# USBasp_B.net
KiCad netlist of a schematic drawn in EAGLE
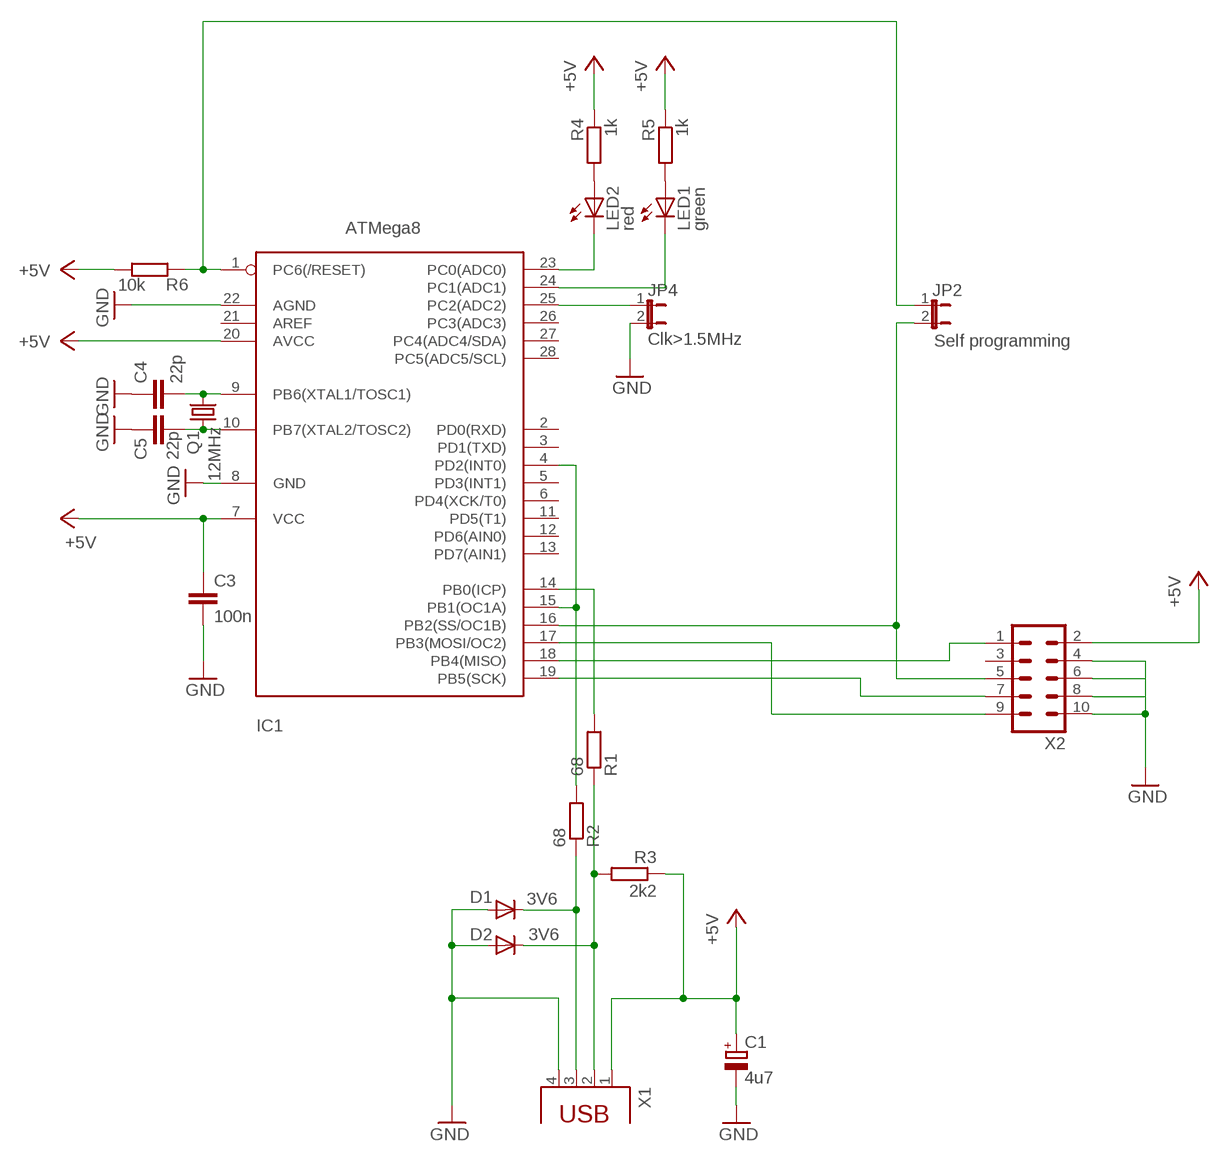
[diagram p0: schematic, sheet 1]

(export (version "E")
  (design (tool "Eeschema 10.0.6"))
  (components
    (comp (ref "C1")
      (value "4u7")
      (footprint "eagle-import:E2,5-5")
      (libsource (lib "eagle-import") (part "CPOL-EUE2.5-5"))
    )
    (comp (ref "C3")
      (value "100n")
      (footprint "eagle-import:C1206K")
      (libsource (lib "eagle-import") (part "C-EUC1206K"))
    )
    (comp (ref "C4")
      (value "22p")
      (footprint "eagle-import:C1206K")
      (libsource (lib "eagle-import") (part "C-EUC1206K"))
    )
    (comp (ref "C5")
      (value "22p")
      (footprint "eagle-import:C1206K")
      (libsource (lib "eagle-import") (part "C-EUC1206K"))
    )
    (comp (ref "D1")
      (value "3V6")
      (footprint "eagle-import:SOD80C")
      (libsource (lib "eagle-import") (part "PMLL41SOD80C"))
    )
    (comp (ref "D2")
      (value "3V6")
      (footprint "eagle-import:SOD80C")
      (libsource (lib "eagle-import") (part "PMLL41SOD80C"))
    )
    (comp (ref "IC1")
      (value "ATMega8")
      (footprint "eagle-import:DIL28-3")
      (libsource (lib "eagle-import") (part "MEGA8-P"))
    )
    (comp (ref "JP2")
      (value "Self programming")
      (footprint "eagle-import:JP1")
      (libsource (lib "eagle-import") (part "JP1E"))
    )
    (comp (ref "JP4")
      (value "Clk>1.5MHz")
      (footprint "eagle-import:JP1")
      (libsource (lib "eagle-import") (part "JP1E"))
    )
    (comp (ref "LED1")
      (value "green")
      (footprint "eagle-import:LED3MM")
      (libsource (lib "eagle-import") (part "LED3MM"))
    )
    (comp (ref "LED2")
      (value "red")
      (footprint "eagle-import:LED3MM")
      (libsource (lib "eagle-import") (part "LED3MM"))
    )
    (comp (ref "Q1")
      (value "12MHz")
      (footprint "eagle-import:HC49_S")
      (libsource (lib "eagle-import") (part "CRYTALHC49S"))
    )
    (comp (ref "R1")
      (value "68")
      (footprint "eagle-import:R1206W")
      (libsource (lib "eagle-import") (part "R-EU_R1206W"))
    )
    (comp (ref "R2")
      (value "68")
      (footprint "eagle-import:R1206W")
      (libsource (lib "eagle-import") (part "R-EU_R1206W"))
    )
    (comp (ref "R3")
      (value "2k2")
      (footprint "eagle-import:R1206W")
      (libsource (lib "eagle-import") (part "R-EU_R1206W"))
    )
    (comp (ref "R4")
      (value "1k")
      (footprint "eagle-import:R1206W")
      (libsource (lib "eagle-import") (part "R-EU_R1206W"))
    )
    (comp (ref "R5")
      (value "1k")
      (footprint "eagle-import:R1206W")
      (libsource (lib "eagle-import") (part "R-EU_R1206W"))
    )
    (comp (ref "R6")
      (value "10k")
      (footprint "eagle-import:R1206W")
      (libsource (lib "eagle-import") (part "R-EU_R1206W"))
    )
    (comp (ref "X1")
      (value "PN61729")
      (footprint "eagle-import:PN61729")
      (libsource (lib "eagle-import") (part "PN61729"))
    )
    (comp (ref "X2")
      (value "ML10")
      (footprint "eagle-import:ML10")
      (libsource (lib "eagle-import") (part "ML10"))
    )
  )
  (nets
    (net (code "1") (name "+5V") (class "Default")
      (node (ref "C1") (pin "+") (pinfunction "+_+") (pintype "passive"))
      (node (ref "C3") (pin "1") (pinfunction "1_1") (pintype "passive"))
      (node (ref "IC1") (pin "20") (pinfunction "AVCC_20") (pintype "bidirectional"))
      (node (ref "IC1") (pin "7") (pinfunction "VCC_7") (pintype "bidirectional"))
      (node (ref "R3") (pin "1") (pinfunction "1_1") (pintype "passive"))
      (node (ref "R4") (pin "1") (pinfunction "1_1") (pintype "passive"))
      (node (ref "R5") (pin "1") (pinfunction "1_1") (pintype "passive"))
      (node (ref "R6") (pin "1") (pinfunction "1_1") (pintype "passive"))
      (node (ref "X1") (pin "1") (pinfunction "1_1") (pintype "bidirectional"))
      (node (ref "X2") (pin "2") (pinfunction "2_2") (pintype "passive"))
    )
    (net (code "2") (name "GND") (class "Default")
      (node (ref "C1") (pin "-") (pinfunction "-_-") (pintype "passive"))
      (node (ref "C3") (pin "2") (pinfunction "2_2") (pintype "passive"))
      (node (ref "C4") (pin "1") (pinfunction "1_1") (pintype "passive"))
      (node (ref "C5") (pin "1") (pinfunction "1_1") (pintype "passive"))
      (node (ref "D1") (pin "A") (pinfunction "A_A") (pintype "passive"))
      (node (ref "D2") (pin "A") (pinfunction "A_A") (pintype "passive"))
      (node (ref "IC1") (pin "22") (pinfunction "AGND_22") (pintype "bidirectional"))
      (node (ref "IC1") (pin "8") (pinfunction "GND_8") (pintype "bidirectional"))
      (node (ref "JP4") (pin "2") (pinfunction "2_2") (pintype "passive"))
      (node (ref "X1") (pin "4") (pinfunction "4_4") (pintype "bidirectional"))
      (node (ref "X2") (pin "10") (pinfunction "10_10") (pintype "passive"))
      (node (ref "X2") (pin "4") (pinfunction "4_4") (pintype "passive"))
      (node (ref "X2") (pin "6") (pinfunction "6_6") (pintype "passive"))
      (node (ref "X2") (pin "8") (pinfunction "8_8") (pintype "passive"))
    )
    (net (code "3") (name "Net-(D1-PadC)") (class "Default")
      (node (ref "D1") (pin "C") (pinfunction "C_C") (pintype "passive"))
      (node (ref "R2") (pin "1") (pinfunction "1_1") (pintype "passive"))
      (node (ref "X1") (pin "3") (pinfunction "3_3") (pintype "bidirectional"))
    )
    (net (code "4") (name "Net-(D2-PadC)") (class "Default")
      (node (ref "D2") (pin "C") (pinfunction "C_C") (pintype "passive"))
      (node (ref "R1") (pin "1") (pinfunction "1_1") (pintype "passive"))
      (node (ref "R3") (pin "2") (pinfunction "2_2") (pintype "passive"))
      (node (ref "X1") (pin "2") (pinfunction "2_2") (pintype "bidirectional"))
    )
    (net (code "5") (name "Net-(IC1-PB0(ICP))") (class "Default")
      (node (ref "IC1") (pin "14") (pinfunction "PB0(ICP)_14") (pintype "bidirectional"))
      (node (ref "R1") (pin "2") (pinfunction "2_2") (pintype "passive"))
    )
    (net (code "6") (name "Net-(IC1-PB1(OC1A))") (class "Default")
      (node (ref "IC1") (pin "15") (pinfunction "PB1(OC1A)_15") (pintype "bidirectional"))
      (node (ref "IC1") (pin "4") (pinfunction "PD2(INT0)_4") (pintype "bidirectional"))
      (node (ref "R2") (pin "2") (pinfunction "2_2") (pintype "passive"))
    )
    (net (code "7") (name "Net-(IC1-PB2(SS{slash}OC1B))") (class "Default")
      (node (ref "IC1") (pin "16") (pinfunction "PB2(SS/OC1B)_16") (pintype "bidirectional"))
      (node (ref "JP2") (pin "2") (pinfunction "2_2") (pintype "passive"))
      (node (ref "X2") (pin "5") (pinfunction "5_5") (pintype "passive"))
    )
    (net (code "8") (name "Net-(IC1-PB3(MOSI{slash}OC2))") (class "Default")
      (node (ref "IC1") (pin "17") (pinfunction "PB3(MOSI/OC2)_17") (pintype "bidirectional"))
      (node (ref "X2") (pin "9") (pinfunction "9_9") (pintype "passive"))
    )
    (net (code "9") (name "Net-(IC1-PB4(MISO))") (class "Default")
      (node (ref "IC1") (pin "18") (pinfunction "PB4(MISO)_18") (pintype "bidirectional"))
      (node (ref "X2") (pin "1") (pinfunction "1_1") (pintype "passive"))
    )
    (net (code "10") (name "Net-(IC1-PB5(SCK))") (class "Default")
      (node (ref "IC1") (pin "19") (pinfunction "PB5(SCK)_19") (pintype "bidirectional"))
      (node (ref "X2") (pin "7") (pinfunction "7_7") (pintype "passive"))
    )
    (net (code "11") (name "Net-(IC1-PB6(XTAL1{slash}TOSC1))") (class "Default")
      (node (ref "C4") (pin "2") (pinfunction "2_2") (pintype "passive"))
      (node (ref "IC1") (pin "9") (pinfunction "PB6(XTAL1/TOSC1)_9") (pintype "bidirectional"))
      (node (ref "Q1") (pin "2") (pinfunction "2_2") (pintype "passive"))
    )
    (net (code "12") (name "Net-(IC1-PB7(XTAL2{slash}TOSC2))") (class "Default")
      (node (ref "C5") (pin "2") (pinfunction "2_2") (pintype "passive"))
      (node (ref "IC1") (pin "10") (pinfunction "PB7(XTAL2/TOSC2)_10") (pintype "bidirectional"))
      (node (ref "Q1") (pin "1") (pinfunction "1_1") (pintype "passive"))
    )
    (net (code "13") (name "Net-(IC1-PC0(ADC0))") (class "Default")
      (node (ref "IC1") (pin "23") (pinfunction "PC0(ADC0)_23") (pintype "bidirectional"))
      (node (ref "LED2") (pin "K") (pinfunction "C_K") (pintype "passive"))
    )
    (net (code "14") (name "Net-(IC1-PC1(ADC1))") (class "Default")
      (node (ref "IC1") (pin "24") (pinfunction "PC1(ADC1)_24") (pintype "bidirectional"))
      (node (ref "LED1") (pin "K") (pinfunction "C_K") (pintype "passive"))
    )
    (net (code "15") (name "Net-(IC1-PC2(ADC2))") (class "Default")
      (node (ref "IC1") (pin "25") (pinfunction "PC2(ADC2)_25") (pintype "bidirectional"))
      (node (ref "JP4") (pin "1") (pinfunction "1_1") (pintype "passive"))
    )
    (net (code "16") (name "Net-(IC1-PC6({slash}RESET))") (class "Default")
      (node (ref "IC1") (pin "1") (pinfunction "PC6(/RESET)_1") (pintype "bidirectional"))
      (node (ref "JP2") (pin "1") (pinfunction "1_1") (pintype "passive"))
      (node (ref "R6") (pin "2") (pinfunction "2_2") (pintype "passive"))
    )
    (net (code "17") (name "Net-(LED1-PadA)") (class "Default")
      (node (ref "LED1") (pin "A") (pinfunction "A_A") (pintype "passive"))
      (node (ref "R5") (pin "2") (pinfunction "2_2") (pintype "passive"))
    )
    (net (code "18") (name "Net-(LED2-PadA)") (class "Default")
      (node (ref "LED2") (pin "A") (pinfunction "A_A") (pintype "passive"))
      (node (ref "R4") (pin "2") (pinfunction "2_2") (pintype "passive"))
    )
    (net (code "19") (name "unconnected-(IC1-AREF-Pad21)") (class "Default")
      (node (ref "IC1") (pin "21") (pinfunction "AREF_21") (pintype "bidirectional"))
    )
    (net (code "20") (name "unconnected-(IC1-PC3(ADC3)-Pad26)") (class "Default")
      (node (ref "IC1") (pin "26") (pinfunction "PC3(ADC3)_26") (pintype "bidirectional"))
    )
    (net (code "21") (name "unconnected-(IC1-PC4(ADC4{slash}SDA)-Pad27)") (class "Default")
      (node (ref "IC1") (pin "27") (pinfunction "PC4(ADC4/SDA)_27") (pintype "bidirectional"))
    )
    (net (code "22") (name "unconnected-(IC1-PC5(ADC5{slash}SCL)-Pad28)") (class "Default")
      (node (ref "IC1") (pin "28") (pinfunction "PC5(ADC5/SCL)_28") (pintype "bidirectional"))
    )
    (net (code "23") (name "unconnected-(IC1-PD0(RXD)-Pad2)") (class "Default")
      (node (ref "IC1") (pin "2") (pinfunction "PD0(RXD)_2") (pintype "bidirectional"))
    )
    (net (code "24") (name "unconnected-(IC1-PD1(TXD)-Pad3)") (class "Default")
      (node (ref "IC1") (pin "3") (pinfunction "PD1(TXD)_3") (pintype "bidirectional"))
    )
    (net (code "25") (name "unconnected-(IC1-PD3(INT1)-Pad5)") (class "Default")
      (node (ref "IC1") (pin "5") (pinfunction "PD3(INT1)_5") (pintype "bidirectional"))
    )
    (net (code "26") (name "unconnected-(IC1-PD4(XCK{slash}T0)-Pad6)") (class "Default")
      (node (ref "IC1") (pin "6") (pinfunction "PD4(XCK/T0)_6") (pintype "bidirectional"))
    )
    (net (code "27") (name "unconnected-(IC1-PD5(T1)-Pad11)") (class "Default")
      (node (ref "IC1") (pin "11") (pinfunction "PD5(T1)_11") (pintype "bidirectional"))
    )
    (net (code "28") (name "unconnected-(IC1-PD6(AIN0)-Pad12)") (class "Default")
      (node (ref "IC1") (pin "12") (pinfunction "PD6(AIN0)_12") (pintype "bidirectional"))
    )
    (net (code "29") (name "unconnected-(IC1-PD7(AIN1)-Pad13)") (class "Default")
      (node (ref "IC1") (pin "13") (pinfunction "PD7(AIN1)_13") (pintype "bidirectional"))
    )
    (net (code "30") (name "unconnected-(X2-Pad3)") (class "Default")
      (node (ref "X2") (pin "3") (pinfunction "3_3") (pintype "passive"))
    )
  )
)
